# DevControl.net
KiCad netlist of a schematic drawn in EAGLE
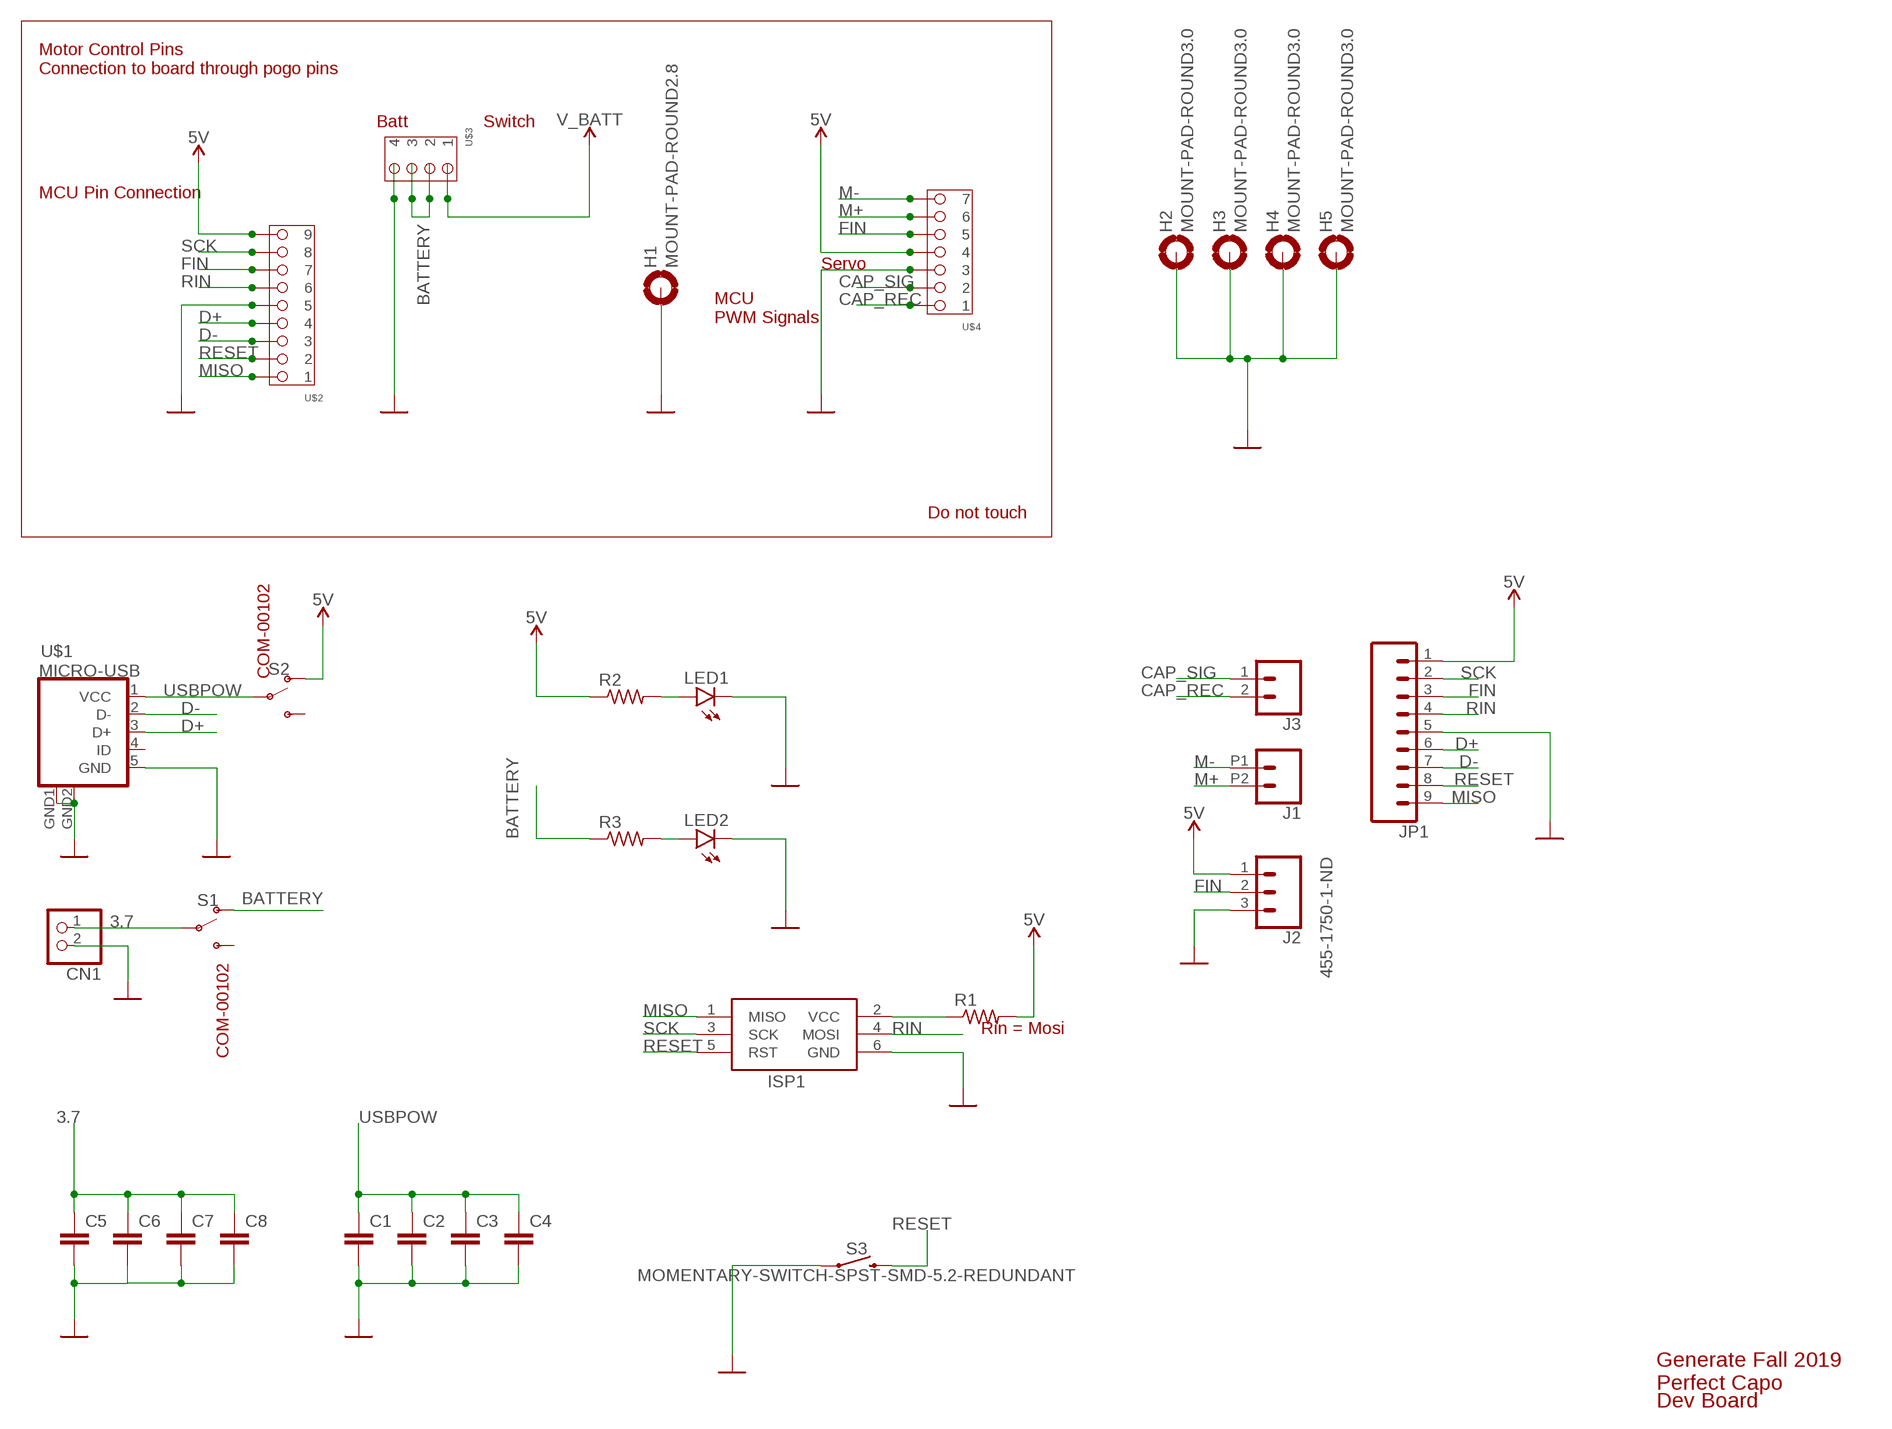
[diagram p0: schematic, sheet 1]

(export (version "E")
  (design (tool "Eeschema 10.0.6"))
  (components
    (comp (ref "C1")
      (value "C-EUC0805")
      (footprint "eagle-import:C0805")
      (libsource (lib "eagle-import") (part "C-EUC0805"))
    )
    (comp (ref "C2")
      (value "C-EUC0805")
      (footprint "eagle-import:C0805")
      (libsource (lib "eagle-import") (part "C-EUC0805"))
    )
    (comp (ref "C3")
      (value "C-EUC0805")
      (footprint "eagle-import:C0805")
      (libsource (lib "eagle-import") (part "C-EUC0805"))
    )
    (comp (ref "C4")
      (value "C-EUC0805")
      (footprint "eagle-import:C0805")
      (libsource (lib "eagle-import") (part "C-EUC0805"))
    )
    (comp (ref "C5")
      (value "C-EUC0805")
      (footprint "eagle-import:C0805")
      (libsource (lib "eagle-import") (part "C-EUC0805"))
    )
    (comp (ref "C6")
      (value "C-EUC0805")
      (footprint "eagle-import:C0805")
      (libsource (lib "eagle-import") (part "C-EUC0805"))
    )
    (comp (ref "C7")
      (value "C-EUC0805")
      (footprint "eagle-import:C0805")
      (libsource (lib "eagle-import") (part "C-EUC0805"))
    )
    (comp (ref "C8")
      (value "C-EUC0805")
      (footprint "eagle-import:C0805")
      (libsource (lib "eagle-import") (part "C-EUC0805"))
    )
    (comp (ref "CN1")
      (value "JST_2PIN-SMT-RA")
      (footprint "eagle-import:JST-PH-2-SMT-RA")
      (libsource (lib "eagle-import") (part "JST_2PIN-SMT-RA"))
    )
    (comp (ref "H1")
      (value "MOUNT-PAD-ROUND2.8")
      (footprint "eagle-import:2,8-PAD")
      (libsource (lib "eagle-import") (part "MOUNT-PAD-ROUND2.8"))
    )
    (comp (ref "H2")
      (value "MOUNT-PAD-ROUND3.0")
      (footprint "eagle-import:3,0-PAD")
      (libsource (lib "eagle-import") (part "MOUNT-PAD-ROUND3.0"))
    )
    (comp (ref "H3")
      (value "MOUNT-PAD-ROUND3.0")
      (footprint "eagle-import:3,0-PAD")
      (libsource (lib "eagle-import") (part "MOUNT-PAD-ROUND3.0"))
    )
    (comp (ref "H4")
      (value "MOUNT-PAD-ROUND3.0")
      (footprint "eagle-import:3,0-PAD")
      (libsource (lib "eagle-import") (part "MOUNT-PAD-ROUND3.0"))
    )
    (comp (ref "H5")
      (value "MOUNT-PAD-ROUND3.0")
      (footprint "eagle-import:3,0-PAD")
      (libsource (lib "eagle-import") (part "MOUNT-PAD-ROUND3.0"))
    )
    (comp (ref "ISP1")
      (value "AVRISP-6")
      (footprint "eagle-import:AVRISP")
      (libsource (lib "eagle-import") (part "AVRISP-6"))
    )
    (comp (ref "J1")
      (value "CONN_022.54MM_SCREWTERM")
      (footprint "eagle-import:1X02_2.54_SCREWTERM")
      (libsource (lib "eagle-import") (part "CONN_022.54MM_SCREWTERM"))
    )
    (comp (ref "J2")
      (value "455-1750-1-ND")
      (footprint "eagle-import:1X03")
      (libsource (lib "eagle-import") (part "CONN_03"))
    )
    (comp (ref "J3")
      (value "CONN_02")
      (footprint "eagle-import:1X02")
      (libsource (lib "eagle-import") (part "CONN_02"))
    )
    (comp (ref "JP1")
      (value "CONN_09")
      (footprint "eagle-import:1X09")
      (libsource (lib "eagle-import") (part "CONN_09"))
    )
    (comp (ref "LED1")
      (value "LEDCHIPLED_0805")
      (footprint "eagle-import:CHIPLED_0805")
      (libsource (lib "eagle-import") (part "LEDCHIPLED_0805"))
    )
    (comp (ref "LED2")
      (value "LEDCHIPLED_0805")
      (footprint "eagle-import:CHIPLED_0805")
      (libsource (lib "eagle-import") (part "LEDCHIPLED_0805"))
    )
    (comp (ref "R1")
      (value "R-US_R0805")
      (footprint "eagle-import:R0805")
      (libsource (lib "eagle-import") (part "R-US_R0805"))
    )
    (comp (ref "R2")
      (value "R-US_R0805")
      (footprint "eagle-import:R0805")
      (libsource (lib "eagle-import") (part "R-US_R0805"))
    )
    (comp (ref "R3")
      (value "R-US_R0805")
      (footprint "eagle-import:R0805")
      (libsource (lib "eagle-import") (part "R-US_R0805"))
    )
    (comp (ref "S1")
      (value "SWITCH-SPDT-PTH-11.6X4.0MM")
      (footprint "eagle-import:SWITCH_SPDT_PTH_11.6X4.0MM")
      (libsource (lib "eagle-import") (part "SWITCH-SPDT-PTH-11.6X4.0MM"))
    )
    (comp (ref "S2")
      (value "SWITCH-SPDT-PTH-11.6X4.0MM")
      (footprint "eagle-import:SWITCH_SPDT_PTH_11.6X4.0MM")
      (libsource (lib "eagle-import") (part "SWITCH-SPDT-PTH-11.6X4.0MM"))
    )
    (comp (ref "S3")
      (value "MOMENTARY-SWITCH-SPST-SMD-5.2-REDUNDANT")
      (footprint "eagle-import:TACTILE_SWITCH_SMD_5.2MM")
      (libsource (lib "eagle-import") (part "MOMENTARY-SWITCH-SPST-SMD-5.2-REDUNDANT"))
    )
    (comp (ref "U$1")
      (value "MICRO-USB")
      (footprint "eagle-import:MICRO-USB")
      (libsource (lib "eagle-import") (part "MICRO-USB"))
    )
    (comp (ref "U$2")
      (value "POGO-1X9")
      (footprint "eagle-import:POGO-1X9")
      (libsource (lib "eagle-import") (part "POGO-1X9"))
    )
    (comp (ref "U$3")
      (value "POGO-1X4")
      (footprint "eagle-import:POGO-1X4")
      (libsource (lib "eagle-import") (part "POGO-1X4"))
    )
    (comp (ref "U$4")
      (value "POGO-1X7")
      (footprint "eagle-import:POGO-1X7")
      (libsource (lib "eagle-import") (part "POGO-1X7"))
    )
  )
  (nets
    (net (code "1") (name "/3.7") (class "Default")
      (node (ref "C5") (pin "1") (pinfunction "1_1") (pintype "passive"))
      (node (ref "C6") (pin "1") (pinfunction "1_1") (pintype "passive"))
      (node (ref "C7") (pin "1") (pinfunction "1_1") (pintype "passive"))
      (node (ref "C8") (pin "1") (pinfunction "1_1") (pintype "passive"))
      (node (ref "CN1") (pin "1") (pinfunction "2_1") (pintype "passive"))
      (node (ref "S1") (pin "2") (pinfunction "P_2") (pintype "passive"))
    )
    (net (code "2") (name "/BATTERY") (class "Default")
      (node (ref "R3") (pin "1") (pinfunction "1_1") (pintype "passive"))
      (node (ref "S1") (pin "1") (pinfunction "O_1") (pintype "passive"))
      (node (ref "U$3") (pin "P$2") (pinfunction "2_P$2") (pintype "bidirectional"))
      (node (ref "U$3") (pin "P$3") (pinfunction "3_P$3") (pintype "bidirectional"))
    )
    (net (code "3") (name "/CAP_REC") (class "Default")
      (node (ref "J3") (pin "2") (pinfunction "2_2") (pintype "passive"))
      (node (ref "U$4") (pin "P$1") (pinfunction "1_P$1") (pintype "bidirectional"))
    )
    (net (code "4") (name "/CAP_SIG") (class "Default")
      (node (ref "J3") (pin "1") (pinfunction "1_1") (pintype "passive"))
      (node (ref "U$4") (pin "P$2") (pinfunction "2_P$2") (pintype "bidirectional"))
    )
    (net (code "5") (name "/D+") (class "Default")
      (node (ref "JP1") (pin "6") (pinfunction "6_6") (pintype "passive"))
      (node (ref "U$1") (pin "3") (pinfunction "D+_3") (pintype "bidirectional"))
      (node (ref "U$2") (pin "P$4") (pinfunction "4_P$4") (pintype "bidirectional"))
    )
    (net (code "6") (name "/D-") (class "Default")
      (node (ref "JP1") (pin "7") (pinfunction "7_7") (pintype "passive"))
      (node (ref "U$1") (pin "2") (pinfunction "D-_2") (pintype "bidirectional"))
      (node (ref "U$2") (pin "P$3") (pinfunction "3_P$3") (pintype "bidirectional"))
    )
    (net (code "7") (name "/FIN") (class "Default")
      (node (ref "J2") (pin "2") (pinfunction "2_2") (pintype "passive"))
      (node (ref "JP1") (pin "3") (pinfunction "3_3") (pintype "passive"))
      (node (ref "U$2") (pin "P$7") (pinfunction "7_P$7") (pintype "bidirectional"))
      (node (ref "U$4") (pin "P$5") (pinfunction "5_P$5") (pintype "bidirectional"))
    )
    (net (code "8") (name "/M+") (class "Default")
      (node (ref "J1") (pin "P2") (pinfunction "2_P2") (pintype "passive"))
      (node (ref "U$4") (pin "P$6") (pinfunction "6_P$6") (pintype "bidirectional"))
    )
    (net (code "9") (name "/M-") (class "Default")
      (node (ref "J1") (pin "P1") (pinfunction "1_P1") (pintype "passive"))
      (node (ref "U$4") (pin "P$7") (pinfunction "7_P$7") (pintype "bidirectional"))
    )
    (net (code "10") (name "/MISO") (class "Default")
      (node (ref "ISP1") (pin "1") (pinfunction "MISO_1") (pintype "input"))
      (node (ref "JP1") (pin "9") (pinfunction "9_9") (pintype "passive"))
      (node (ref "U$2") (pin "P$1") (pinfunction "1_P$1") (pintype "bidirectional"))
    )
    (net (code "11") (name "/RESET") (class "Default")
      (node (ref "ISP1") (pin "5") (pinfunction "RST_5") (pintype "output"))
      (node (ref "JP1") (pin "8") (pinfunction "8_8") (pintype "passive"))
      (node (ref "S3") (pin "3") (pinfunction "2_3") (pintype "passive"))
      (node (ref "S3") (pin "4") (pinfunction "2_4") (pintype "passive"))
      (node (ref "U$2") (pin "P$2") (pinfunction "2_P$2") (pintype "bidirectional"))
    )
    (net (code "12") (name "/RIN") (class "Default")
      (node (ref "ISP1") (pin "4") (pinfunction "MOSI_4") (pintype "output"))
      (node (ref "JP1") (pin "4") (pinfunction "4_4") (pintype "passive"))
      (node (ref "U$2") (pin "P$6") (pinfunction "6_P$6") (pintype "bidirectional"))
    )
    (net (code "13") (name "/SCK") (class "Default")
      (node (ref "ISP1") (pin "3") (pinfunction "SCK_3") (pintype "output"))
      (node (ref "JP1") (pin "2") (pinfunction "2_2") (pintype "passive"))
      (node (ref "U$2") (pin "P$8") (pinfunction "8_P$8") (pintype "bidirectional"))
    )
    (net (code "14") (name "/USBPOW") (class "Default")
      (node (ref "C1") (pin "1") (pinfunction "1_1") (pintype "passive"))
      (node (ref "C2") (pin "1") (pinfunction "1_1") (pintype "passive"))
      (node (ref "C3") (pin "1") (pinfunction "1_1") (pintype "passive"))
      (node (ref "C4") (pin "1") (pinfunction "1_1") (pintype "passive"))
      (node (ref "S2") (pin "2") (pinfunction "P_2") (pintype "passive"))
      (node (ref "U$1") (pin "1") (pinfunction "VCC_1") (pintype "power_in"))
    )
    (net (code "15") (name "5V") (class "Default")
      (node (ref "J2") (pin "1") (pinfunction "1_1") (pintype "passive"))
      (node (ref "JP1") (pin "1") (pinfunction "1_1") (pintype "passive"))
      (node (ref "R1") (pin "2") (pinfunction "2_2") (pintype "passive"))
      (node (ref "R2") (pin "1") (pinfunction "1_1") (pintype "passive"))
      (node (ref "S2") (pin "1") (pinfunction "O_1") (pintype "passive"))
      (node (ref "U$2") (pin "P$9") (pinfunction "9_P$9") (pintype "bidirectional"))
      (node (ref "U$4") (pin "P$4") (pinfunction "4_P$4") (pintype "bidirectional"))
    )
    (net (code "16") (name "GND") (class "Default")
      (node (ref "C1") (pin "2") (pinfunction "2_2") (pintype "passive"))
      (node (ref "C2") (pin "2") (pinfunction "2_2") (pintype "passive"))
      (node (ref "C3") (pin "2") (pinfunction "2_2") (pintype "passive"))
      (node (ref "C4") (pin "2") (pinfunction "2_2") (pintype "passive"))
      (node (ref "C5") (pin "2") (pinfunction "2_2") (pintype "passive"))
      (node (ref "C6") (pin "2") (pinfunction "2_2") (pintype "passive"))
      (node (ref "C7") (pin "2") (pinfunction "2_2") (pintype "passive"))
      (node (ref "C8") (pin "2") (pinfunction "2_2") (pintype "passive"))
      (node (ref "CN1") (pin "2") (pinfunction "1_2") (pintype "passive"))
      (node (ref "H1") (pin "B2,8") (pinfunction "MOUNT_B2,8") (pintype "passive"))
      (node (ref "H2") (pin "B3,0") (pinfunction "MOUNT_B3,0") (pintype "passive"))
      (node (ref "H3") (pin "B3,0") (pinfunction "MOUNT_B3,0") (pintype "passive"))
      (node (ref "H4") (pin "B3,0") (pinfunction "MOUNT_B3,0") (pintype "passive"))
      (node (ref "H5") (pin "B3,0") (pinfunction "MOUNT_B3,0") (pintype "passive"))
      (node (ref "ISP1") (pin "6") (pinfunction "GND_6") (pintype "power_in"))
      (node (ref "J2") (pin "3") (pinfunction "3_3") (pintype "passive"))
      (node (ref "JP1") (pin "5") (pinfunction "5_5") (pintype "passive"))
      (node (ref "LED1") (pin "C") (pinfunction "C_C") (pintype "passive"))
      (node (ref "LED2") (pin "C") (pinfunction "C_C") (pintype "passive"))
      (node (ref "S3") (pin "1") (pinfunction "1_1") (pintype "passive"))
      (node (ref "S3") (pin "2") (pinfunction "1_2") (pintype "passive"))
      (node (ref "U$1") (pin "5") (pinfunction "GND_5") (pintype "power_in"))
      (node (ref "U$1") (pin "GND1") (pinfunction "GND_GND1") (pintype "power_in"))
      (node (ref "U$1") (pin "GND2") (pinfunction "GND_GND2") (pintype "power_in"))
      (node (ref "U$2") (pin "P$5") (pinfunction "5_P$5") (pintype "bidirectional"))
      (node (ref "U$3") (pin "P$4") (pinfunction "4_P$4") (pintype "bidirectional"))
      (node (ref "U$4") (pin "P$3") (pinfunction "3_P$3") (pintype "bidirectional"))
    )
    (net (code "17") (name "Net-(ISP1-VCC)") (class "Default")
      (node (ref "ISP1") (pin "2") (pinfunction "VCC_2") (pintype "power_in"))
      (node (ref "R1") (pin "1") (pinfunction "1_1") (pintype "passive"))
    )
    (net (code "18") (name "Net-(LED1-PadA)") (class "Default")
      (node (ref "LED1") (pin "A") (pinfunction "A_A") (pintype "passive"))
      (node (ref "R2") (pin "2") (pinfunction "2_2") (pintype "passive"))
    )
    (net (code "19") (name "Net-(LED2-PadA)") (class "Default")
      (node (ref "LED2") (pin "A") (pinfunction "A_A") (pintype "passive"))
      (node (ref "R3") (pin "2") (pinfunction "2_2") (pintype "passive"))
    )
    (net (code "20") (name "V_BATT") (class "Default")
      (node (ref "U$3") (pin "P$1") (pinfunction "1_P$1") (pintype "bidirectional"))
    )
    (net (code "21") (name "unconnected-(S1-S-Pad3)") (class "Default")
      (node (ref "S1") (pin "3") (pinfunction "S_3") (pintype "passive"))
    )
    (net (code "22") (name "unconnected-(S2-S-Pad3)") (class "Default")
      (node (ref "S2") (pin "3") (pinfunction "S_3") (pintype "passive"))
    )
    (net (code "23") (name "unconnected-(U$1-ID-Pad4)") (class "Default")
      (node (ref "U$1") (pin "4") (pinfunction "ID_4") (pintype "bidirectional"))
    )
  )
)
